# PowerManagement.net
KiCad netlist of a schematic drawn in Altium Designer
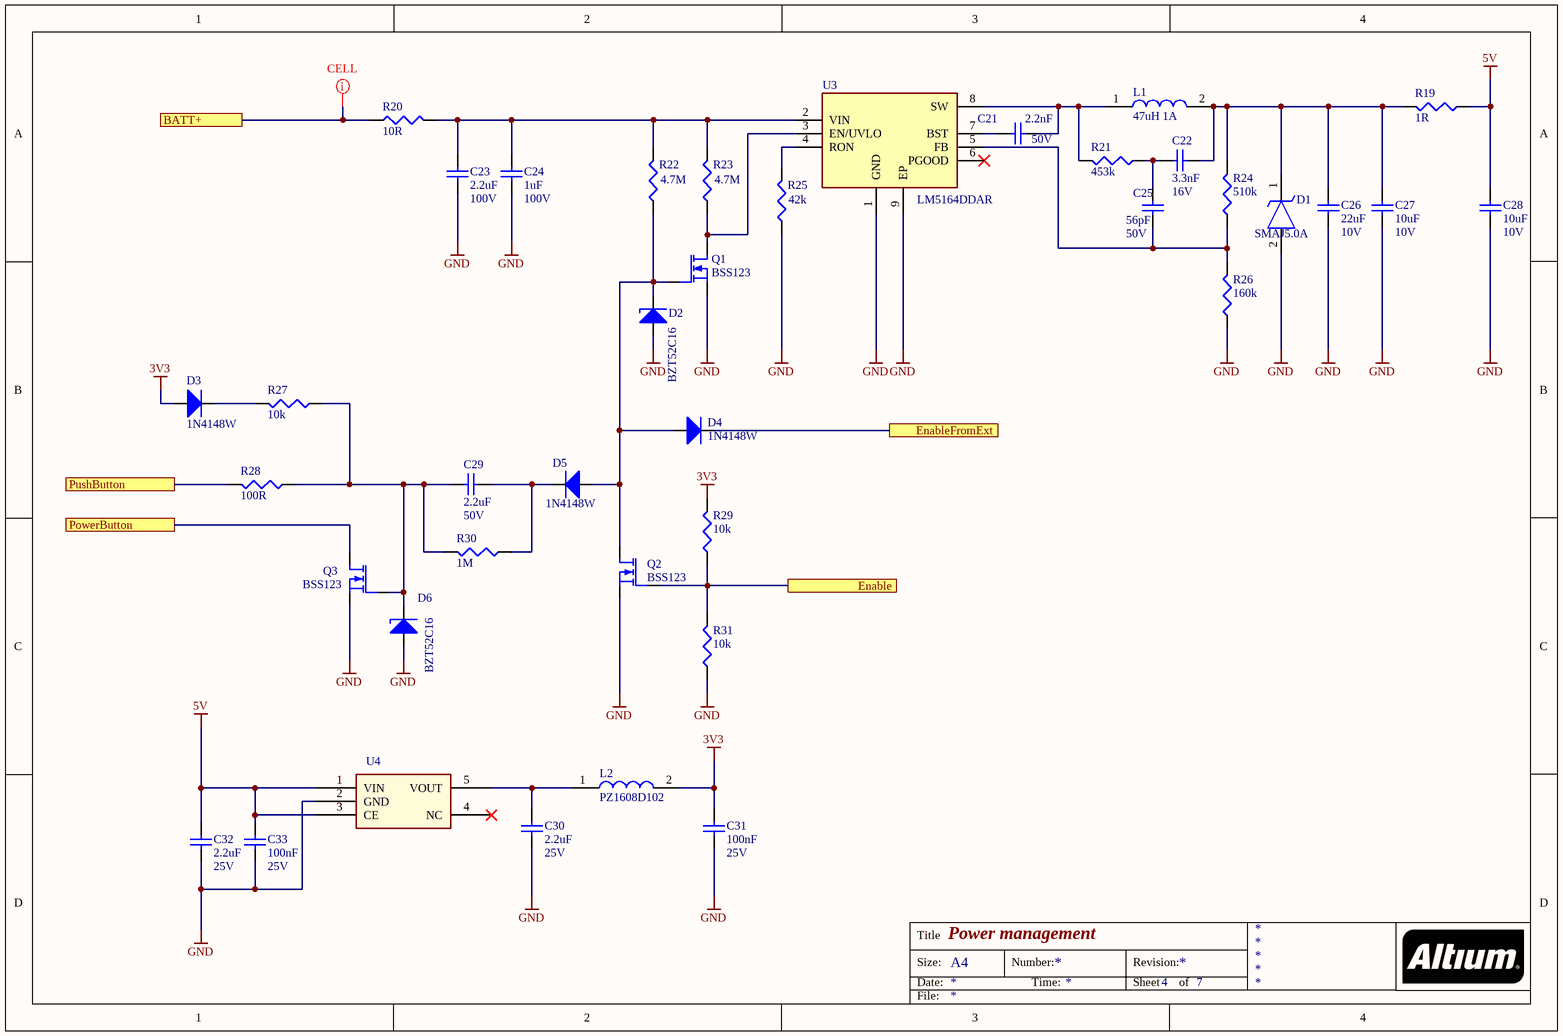
[diagram p0: PowerManagement.SchDoc]

(export (version "E")
  (design (tool "Eeschema 10.0.6"))
  (components
    (comp (ref "C21")
      (value "2.2nF")
      (footprint "VESC_BMS:C0402")
      (description "Capacitor, 100nF, 25V, X7R")
      (fields (field (name "VOLTAGE RATING") "50V"))
      (libsource (lib "AR_Capacitors_Ceramic") (part "100nF/0402/CER/25V"))
    )
    (comp (ref "C22")
      (value "3.3nF")
      (footprint "VESC_BMS:C0402")
      (description "Capacitor, 100nF, 25V, X7R")
      (fields (field (name "VOLTAGE RATING") "16V"))
      (libsource (lib "AR_Capacitors_Ceramic") (part "100nF/0402/CER/25V"))
    )
    (comp (ref "C23")
      (value "2.2uF")
      (footprint "VESC_BMS:C-1206")
      (description "Capacitor, 1uF, 100V, X7R")
      (fields (field (name "VOLTAGE RATING") "100V"))
      (libsource (lib "AR_Capacitors_Ceramic") (part "1uF/1206/CER/100V"))
    )
    (comp (ref "C24")
      (value "1uF")
      (footprint "VESC_BMS:C-1206")
      (description "Capacitor, 1uF, 100V, X7R")
      (fields (field (name "VOLTAGE RATING") "100V"))
      (libsource (lib "AR_Capacitors_Ceramic") (part "1uF/1206/CER/100V"))
    )
    (comp (ref "C25")
      (value "56pF")
      (footprint "VESC_BMS:C0402")
      (description "Capacitor, 100nF, 25V, X7R")
      (fields (field (name "VOLTAGE RATING") "50V"))
      (libsource (lib "AR_Capacitors_Ceramic") (part "100nF/0402/CER/25V"))
    )
    (comp (ref "C26")
      (value "22uF")
      (footprint "VESC_BMS:C-0805")
      (description "Capacitor, 10uF, 10V, X7R")
      (fields (field (name "VOLTAGE RATING") "10V"))
      (libsource (lib "AR_Capacitors_Ceramic") (part "10uF/0805/CER/10V"))
    )
    (comp (ref "C27")
      (value "10uF")
      (footprint "VESC_BMS:C-0805")
      (description "Capacitor, 10uF, 10V, X7R")
      (fields (field (name "VOLTAGE RATING") "10V"))
      (libsource (lib "AR_Capacitors_Ceramic") (part "10uF/0805/CER/10V"))
    )
    (comp (ref "C28")
      (value "10uF")
      (footprint "VESC_BMS:C-0805")
      (description "Capacitor, 10uF, 10V, X7R")
      (fields (field (name "VOLTAGE RATING") "10V"))
      (libsource (lib "AR_Capacitors_Ceramic") (part "10uF/0805/CER/10V"))
    )
    (comp (ref "C29")
      (value "2.2uF")
      (footprint "VESC_BMS:C-0805")
      (description "Capacitor, 2.2uF, 50V,  X7R")
      (fields (field (name "VOLTAGE RATING") "50V"))
      (libsource (lib "AR_Capacitors_Ceramic") (part "2.2uF/0805/CER/50V"))
    )
    (comp (ref "C30")
      (value "2.2uF")
      (footprint "VESC_BMS:C0402")
      (description "Capacitor, 100nF, 25V, X7R")
      (fields (field (name "VOLTAGE RATING") "25V"))
      (libsource (lib "AR_Capacitors_Ceramic") (part "100nF/0402/CER/25V"))
    )
    (comp (ref "C31")
      (value "100nF")
      (footprint "VESC_BMS:C0402")
      (description "Capacitor, 100nF, 25V, X7R")
      (fields (field (name "VOLTAGE RATING") "25V"))
      (libsource (lib "AR_Capacitors_Ceramic") (part "100nF/0402/CER/25V"))
    )
    (comp (ref "C32")
      (value "2.2uF")
      (footprint "VESC_BMS:C0402")
      (description "Capacitor, 100nF, 25V, X7R")
      (fields (field (name "VOLTAGE RATING") "25V"))
      (libsource (lib "AR_Capacitors_Ceramic") (part "100nF/0402/CER/25V"))
    )
    (comp (ref "C33")
      (value "100nF")
      (footprint "VESC_BMS:C0402")
      (description "Capacitor, 100nF, 25V, X7R")
      (fields (field (name "VOLTAGE RATING") "25V"))
      (libsource (lib "AR_Capacitors_Ceramic") (part "100nF/0402/CER/25V"))
    )
    (comp (ref "D1")
      (value "SMAJ5.0A")
      (footprint "VESC_BMS:SOD-123F")
      (description "TVS Diode (Uni-directional)")
      (fields
        (field (name "MANUFACTURER_PART_NUMBER") "SMAJ7.0A")
        (field (name "MOUSER PART NUMBER") "576-SMAJ7.0A")
      )
      (libsource (lib "VESC_BMS") (part "SMAJ5.0A"))
    )
    (comp (ref "D2")
      (value "BZT52C16")
      (footprint "VESC_BMS:SOD123")
      (description "Diode Zener, Vz: 16V, If: 0.1A, Vf: 0.9V")
      (libsource (lib "AR_Diodes") (part "BZT52C16"))
    )
    (comp (ref "D3")
      (value "1N4148W")
      (footprint "VESC_BMS:SOD123")
      (description "Diode, Vrrm: 100V, If: 0.15A, Vf: 1V")
      (libsource (lib "AR_Diodes") (part "MMSD4148T1G"))
    )
    (comp (ref "D4")
      (value "1N4148W")
      (footprint "VESC_BMS:SOD123")
      (description "Diode, Vrrm: 100V, If: 0.15A, Vf: 1V")
      (libsource (lib "AR_Diodes") (part "MMSD4148T1G"))
    )
    (comp (ref "D5")
      (value "1N4148W")
      (footprint "VESC_BMS:SOD123")
      (description "Diode, Vrrm: 100V, If: 0.15A, Vf: 1V")
      (libsource (lib "AR_Diodes") (part "MMSD4148T1G"))
    )
    (comp (ref "D6")
      (value "BZT52C16")
      (footprint "VESC_BMS:SOD123")
      (description "Diode Zener, Vz: 16V, If: 0.1A, Vf: 0.9V")
      (libsource (lib "AR_Diodes") (part "BZT52C16"))
    )
    (comp (ref "L1")
      (value "47uH 1A")
      (footprint "VESC_BMS:L5040")
      (description "Inductor")
      (fields
        (field (name "MANUFACTURER_PART_NUMBER") "74404054221")
        (field (name "MOUSER PART NUMBER") "710-74404054221")
      )
      (libsource (lib "VESC_BMS") (part "74404054221"))
    )
    (comp (ref "L2")
      (value "PZ1608D102")
      (footprint "VESC_BMS:L0603")
      (description "Inductor")
      (fields
        (field (name "MANUFACTURER_PART_NUMBER") "LQG15HS4N7C02D")
        (field (name "MOUSER PART NUMBER") "81-LQG15HS4N7C02D")
      )
      (libsource (lib "VESC_BMS") (part "PZ1608D102"))
    )
    (comp (ref "Q1")
      (value "BSS123")
      (footprint "VESC_BMS:SOT-23")
      (description "Mosfet, N-channel, Vds:100V, Id:0.15A, Vgs-th:2.8V, Rds-on:3.5ohm")
      (libsource (lib "AR_Mosfets") (part "BSS123"))
    )
    (comp (ref "Q2")
      (value "BSS123")
      (footprint "VESC_BMS:SOT-23")
      (description "Mosfet, N-channel, Vds:100V, Id:0.15A, Vgs-th:2.8V, Rds-on:3.5ohm")
      (libsource (lib "AR_Mosfets") (part "BSS123"))
    )
    (comp (ref "Q3")
      (value "BSS123")
      (footprint "VESC_BMS:SOT-23")
      (description "Mosfet, N-channel, Vds:100V, Id:0.15A, Vgs-th:2.8V, Rds-on:3.5ohm")
      (libsource (lib "AR_Mosfets") (part "BSS123"))
    )
    (comp (ref "R19")
      (value "1R")
      (footprint "VESC_BMS:0805")
      (description "Resistor, 1R, 1%, 0.25W, 150V, 200PPM, 0805")
      (libsource (lib "AR_Resistors_SMD") (part "1/0805/0250W/150V"))
    )
    (comp (ref "R20")
      (value "10R")
      (footprint "R1206")
      (description "Resistor")
      (fields (field (name "MANUFACTURER_PART_NUMBER") "RQ73C2B10RBTDF"))
      (libsource (lib "VESC_BMS") (part "RQ73C2B10RBTDF"))
    )
    (comp (ref "R21")
      (value "453k")
      (footprint "VESC_BMS:0402")
      (description "Resistor, 1M, 0.1%, 0.0625W, 50V, 100PPM, 0402")
      (libsource (lib "AR_Resistors_SMD") (part "1M/0402/0063W/50V"))
    )
    (comp (ref "R22")
      (value "4.7M")
      (footprint "VESC_BMS:0402")
      (description "Resistor, 1M, 0.1%, 0.0625W, 50V, 100PPM, 0402")
      (libsource (lib "AR_Resistors_SMD") (part "1M/0402/0063W/50V"))
    )
    (comp (ref "R23")
      (value "4.7M")
      (footprint "VESC_BMS:0402")
      (description "Resistor, 1M, 0.1%, 0.0625W, 50V, 100PPM, 0402")
      (libsource (lib "AR_Resistors_SMD") (part "1M/0402/0063W/50V"))
    )
    (comp (ref "R24")
      (value "510k")
      (footprint "VESC_BMS:0402")
      (description "Resistor, 1M, 0.1%, 0.0625W, 50V, 100PPM, 0402")
      (libsource (lib "AR_Resistors_SMD") (part "1M/0402/0063W/50V"))
    )
    (comp (ref "R25")
      (value "42k")
      (footprint "VESC_BMS:0402")
      (description "Resistor, 1M, 0.1%, 0.0625W, 50V, 100PPM, 0402")
      (libsource (lib "AR_Resistors_SMD") (part "1M/0402/0063W/50V"))
    )
    (comp (ref "R26")
      (value "160k")
      (footprint "VESC_BMS:0402")
      (description "Resistor, 1M, 0.1%, 0.0625W, 50V, 100PPM, 0402")
      (libsource (lib "AR_Resistors_SMD") (part "1M/0402/0063W/50V"))
    )
    (comp (ref "R27")
      (value "10k")
      (footprint "VESC_BMS:0402")
      (description "Resistor, 10k, 0.1%, 0.0625W, 50V, 100PPM, 0402")
      (libsource (lib "AR_Resistors_SMD") (part "10k/0402/0063W/50V"))
    )
    (comp (ref "R28")
      (value "100R")
      (footprint "VESC_BMS:0603")
      (description "Resistor, 100R, 1%, 0.063W, 50V, 200PPM, 0603")
      (libsource (lib "AR_Resistors_SMD") (part "100/0603/0063W/50V"))
    )
    (comp (ref "R29")
      (value "10k")
      (footprint "VESC_BMS:0402")
      (description "Resistor, 10k, 0.1%, 0.0625W, 50V, 100PPM, 0402")
      (libsource (lib "AR_Resistors_SMD") (part "10k/0402/0063W/50V"))
    )
    (comp (ref "R30")
      (value "1M")
      (footprint "VESC_BMS:0402")
      (description "Resistor, 1M, 0.1%, 0.0625W, 50V, 100PPM, 0402")
      (libsource (lib "AR_Resistors_SMD") (part "1M/0402/0063W/50V"))
    )
    (comp (ref "R31")
      (value "10k")
      (footprint "VESC_BMS:0402")
      (description "Resistor, 10k, 0.1%, 0.0625W, 50V, 100PPM, 0402")
      (libsource (lib "AR_Resistors_SMD") (part "10k/0402/0063W/50V"))
    )
    (comp (ref "U3")
      (value "LM5164DDAR")
      (footprint "VESC_BMS:SOIC127P600X170-9N")
      (description "Integrated Circuit")
      (fields (field (name "MOUSER PART NUMBER") "595-LM5164DDAR"))
      (libsource (lib "VESC_BMS") (part "LM5164DDAR"))
    )
    (comp (ref "U4")
      (value "XC6219B332MR")
      (footprint "VESC_BMS:SOT-23-5")
      (libsource (lib "VESC_BMS") (part "XC6219B332MR"))
    )
  )
  (nets
    (net (code "1") (name "/BATT+") (class "Default")
      (node (ref "R20") (pin "1") (pinfunction "1_1") (pintype "passive"))
    )
    (net (code "2") (name "/Enable") (class "Default")
      (node (ref "Q2") (pin "G") (pinfunction "G_G") (pintype "passive"))
      (node (ref "R29") (pin "1") (pinfunction "1_1") (pintype "passive"))
      (node (ref "R31") (pin "2") (pinfunction "2_2") (pintype "passive"))
    )
    (net (code "3") (name "/EnableFromExt") (class "Default")
      (node (ref "D4") (pin "2") (pinfunction "K_2") (pintype "passive"))
    )
    (net (code "4") (name "/PowerButton") (class "Default")
      (node (ref "Q3") (pin "D") (pinfunction "D_D") (pintype "passive"))
    )
    (net (code "5") (name "/PushButton") (class "Default")
      (node (ref "R28") (pin "2") (pinfunction "2_2") (pintype "passive"))
    )
    (net (code "6") (name "3V3") (class "Default")
      (node (ref "C31") (pin "1") (pinfunction "1_1") (pintype "passive"))
      (node (ref "D3") (pin "1") (pinfunction "A_1") (pintype "passive"))
      (node (ref "L2") (pin "2") (pinfunction "2_2") (pintype "passive"))
      (node (ref "R29") (pin "2") (pinfunction "2_2") (pintype "passive"))
    )
    (net (code "7") (name "5V") (class "Default")
      (node (ref "C28") (pin "2") (pinfunction "2_2") (pintype "passive"))
      (node (ref "C32") (pin "1") (pinfunction "1_1") (pintype "passive"))
      (node (ref "C33") (pin "1") (pinfunction "1_1") (pintype "passive"))
      (node (ref "R19") (pin "1") (pinfunction "1_1") (pintype "passive"))
      (node (ref "U4") (pin "1") (pinfunction "VIN_1") (pintype "passive"))
      (node (ref "U4") (pin "3") (pinfunction "CE_3") (pintype "passive"))
    )
    (net (code "8") (name "GND") (class "Default")
      (node (ref "C23") (pin "1") (pinfunction "1_1") (pintype "passive"))
      (node (ref "C24") (pin "1") (pinfunction "1_1") (pintype "passive"))
      (node (ref "C26") (pin "1") (pinfunction "1_1") (pintype "passive"))
      (node (ref "C27") (pin "1") (pinfunction "1_1") (pintype "passive"))
      (node (ref "C28") (pin "1") (pinfunction "1_1") (pintype "passive"))
      (node (ref "C30") (pin "2") (pinfunction "2_2") (pintype "passive"))
      (node (ref "C31") (pin "2") (pinfunction "2_2") (pintype "passive"))
      (node (ref "C32") (pin "2") (pinfunction "2_2") (pintype "passive"))
      (node (ref "C33") (pin "2") (pinfunction "2_2") (pintype "passive"))
      (node (ref "D1") (pin "2") (pinfunction "A_2") (pintype "passive"))
      (node (ref "D2") (pin "1") (pinfunction "A_1") (pintype "passive"))
      (node (ref "D6") (pin "1") (pinfunction "A_1") (pintype "passive"))
      (node (ref "Q1") (pin "S") (pinfunction "S_S") (pintype "passive"))
      (node (ref "Q2") (pin "S") (pinfunction "S_S") (pintype "passive"))
      (node (ref "Q3") (pin "S") (pinfunction "S_S") (pintype "passive"))
      (node (ref "R25") (pin "1") (pinfunction "1_1") (pintype "passive"))
      (node (ref "R26") (pin "1") (pinfunction "1_1") (pintype "passive"))
      (node (ref "R31") (pin "1") (pinfunction "1_1") (pintype "passive"))
      (node (ref "U3") (pin "1") (pinfunction "GND_1") (pintype "passive"))
      (node (ref "U3") (pin "9") (pinfunction "EP_9") (pintype "passive"))
      (node (ref "U4") (pin "2") (pinfunction "GND_2") (pintype "passive"))
    )
    (net (code "9") (name "Net-(C22-Pad1)") (class "Default")
      (node (ref "C22") (pin "1") (pinfunction "1_1") (pintype "passive"))
      (node (ref "C25") (pin "1") (pinfunction "1_1") (pintype "passive"))
      (node (ref "R21") (pin "1") (pinfunction "1_1") (pintype "passive"))
    )
    (net (code "10") (name "Net-(D1-K)") (class "Default")
      (node (ref "C22") (pin "2") (pinfunction "2_2") (pintype "passive"))
      (node (ref "C26") (pin "2") (pinfunction "2_2") (pintype "passive"))
      (node (ref "C27") (pin "2") (pinfunction "2_2") (pintype "passive"))
      (node (ref "D1") (pin "1") (pinfunction "K_1") (pintype "passive"))
      (node (ref "L1") (pin "2") (pinfunction "2_2") (pintype "passive"))
      (node (ref "R19") (pin "2") (pinfunction "2_2") (pintype "passive"))
      (node (ref "R24") (pin "2") (pinfunction "2_2") (pintype "passive"))
    )
    (net (code "11") (name "Net-(D2-K)") (class "Default")
      (node (ref "D2") (pin "2") (pinfunction "K_2") (pintype "passive"))
      (node (ref "D4") (pin "1") (pinfunction "A_1") (pintype "passive"))
      (node (ref "D5") (pin "1") (pinfunction "A_1") (pintype "passive"))
      (node (ref "Q1") (pin "G") (pinfunction "G_G") (pintype "passive"))
      (node (ref "Q2") (pin "D") (pinfunction "D_D") (pintype "passive"))
      (node (ref "R22") (pin "1") (pinfunction "1_1") (pintype "passive"))
    )
    (net (code "12") (name "Net-(D3-K)") (class "Default")
      (node (ref "D3") (pin "2") (pinfunction "K_2") (pintype "passive"))
      (node (ref "R27") (pin "1") (pinfunction "1_1") (pintype "passive"))
    )
    (net (code "13") (name "Net-(D5-K)") (class "Default")
      (node (ref "C29") (pin "2") (pinfunction "2_2") (pintype "passive"))
      (node (ref "D5") (pin "2") (pinfunction "K_2") (pintype "passive"))
      (node (ref "R30") (pin "1") (pinfunction "1_1") (pintype "passive"))
    )
    (net (code "14") (name "Net-(D6-K)") (class "Default")
      (node (ref "C29") (pin "1") (pinfunction "1_1") (pintype "passive"))
      (node (ref "D6") (pin "2") (pinfunction "K_2") (pintype "passive"))
      (node (ref "Q3") (pin "G") (pinfunction "G_G") (pintype "passive"))
      (node (ref "R27") (pin "2") (pinfunction "2_2") (pintype "passive"))
      (node (ref "R28") (pin "1") (pinfunction "1_1") (pintype "passive"))
      (node (ref "R30") (pin "2") (pinfunction "2_2") (pintype "passive"))
    )
    (net (code "15") (name "Net-(U3-BST)") (class "Default")
      (node (ref "C21") (pin "1") (pinfunction "1_1") (pintype "passive"))
      (node (ref "U3") (pin "7") (pinfunction "BST_7") (pintype "passive"))
    )
    (net (code "16") (name "Net-(U3-EN{slash}UVLO)") (class "Default")
      (node (ref "Q1") (pin "D") (pinfunction "D_D") (pintype "passive"))
      (node (ref "R23") (pin "1") (pinfunction "1_1") (pintype "passive"))
      (node (ref "U3") (pin "3") (pinfunction "EN/UVLO_3") (pintype "passive"))
    )
    (net (code "17") (name "Net-(U3-FB)") (class "Default")
      (node (ref "C25") (pin "2") (pinfunction "2_2") (pintype "passive"))
      (node (ref "R24") (pin "1") (pinfunction "1_1") (pintype "passive"))
      (node (ref "R26") (pin "2") (pinfunction "2_2") (pintype "passive"))
      (node (ref "U3") (pin "5") (pinfunction "FB_5") (pintype "passive"))
    )
    (net (code "18") (name "Net-(U3-RON)") (class "Default")
      (node (ref "R25") (pin "2") (pinfunction "2_2") (pintype "passive"))
      (node (ref "U3") (pin "4") (pinfunction "RON_4") (pintype "passive"))
    )
    (net (code "19") (name "Net-(U3-SW)") (class "Default")
      (node (ref "C21") (pin "2") (pinfunction "2_2") (pintype "passive"))
      (node (ref "L1") (pin "1") (pinfunction "1_1") (pintype "passive"))
      (node (ref "R21") (pin "2") (pinfunction "2_2") (pintype "passive"))
      (node (ref "U3") (pin "8") (pinfunction "SW_8") (pintype "passive"))
    )
    (net (code "20") (name "Net-(U3-VIN)") (class "Default")
      (node (ref "C23") (pin "2") (pinfunction "2_2") (pintype "passive"))
      (node (ref "C24") (pin "2") (pinfunction "2_2") (pintype "passive"))
      (node (ref "R20") (pin "2") (pinfunction "2_2") (pintype "passive"))
      (node (ref "R22") (pin "2") (pinfunction "2_2") (pintype "passive"))
      (node (ref "R23") (pin "2") (pinfunction "2_2") (pintype "passive"))
      (node (ref "U3") (pin "2") (pinfunction "VIN_2") (pintype "passive"))
    )
    (net (code "21") (name "Net-(U4-VOUT)") (class "Default")
      (node (ref "C30") (pin "1") (pinfunction "1_1") (pintype "passive"))
      (node (ref "L2") (pin "1") (pinfunction "1_1") (pintype "passive"))
      (node (ref "U4") (pin "5") (pinfunction "VOUT_5") (pintype "passive"))
    )
    (net (code "22") (name "unconnected-(U3-PGOOD-Pad6)") (class "Default")
      (node (ref "U3") (pin "6") (pinfunction "PGOOD_6") (pintype "passive+no_connect"))
    )
    (net (code "23") (name "unconnected-(U4-NC-Pad4)") (class "Default")
      (node (ref "U4") (pin "4") (pinfunction "NC_4") (pintype "passive+no_connect"))
    )
  )
)
